# Decoupling_caps.net
KiCad netlist of a schematic drawn in Altium Designer
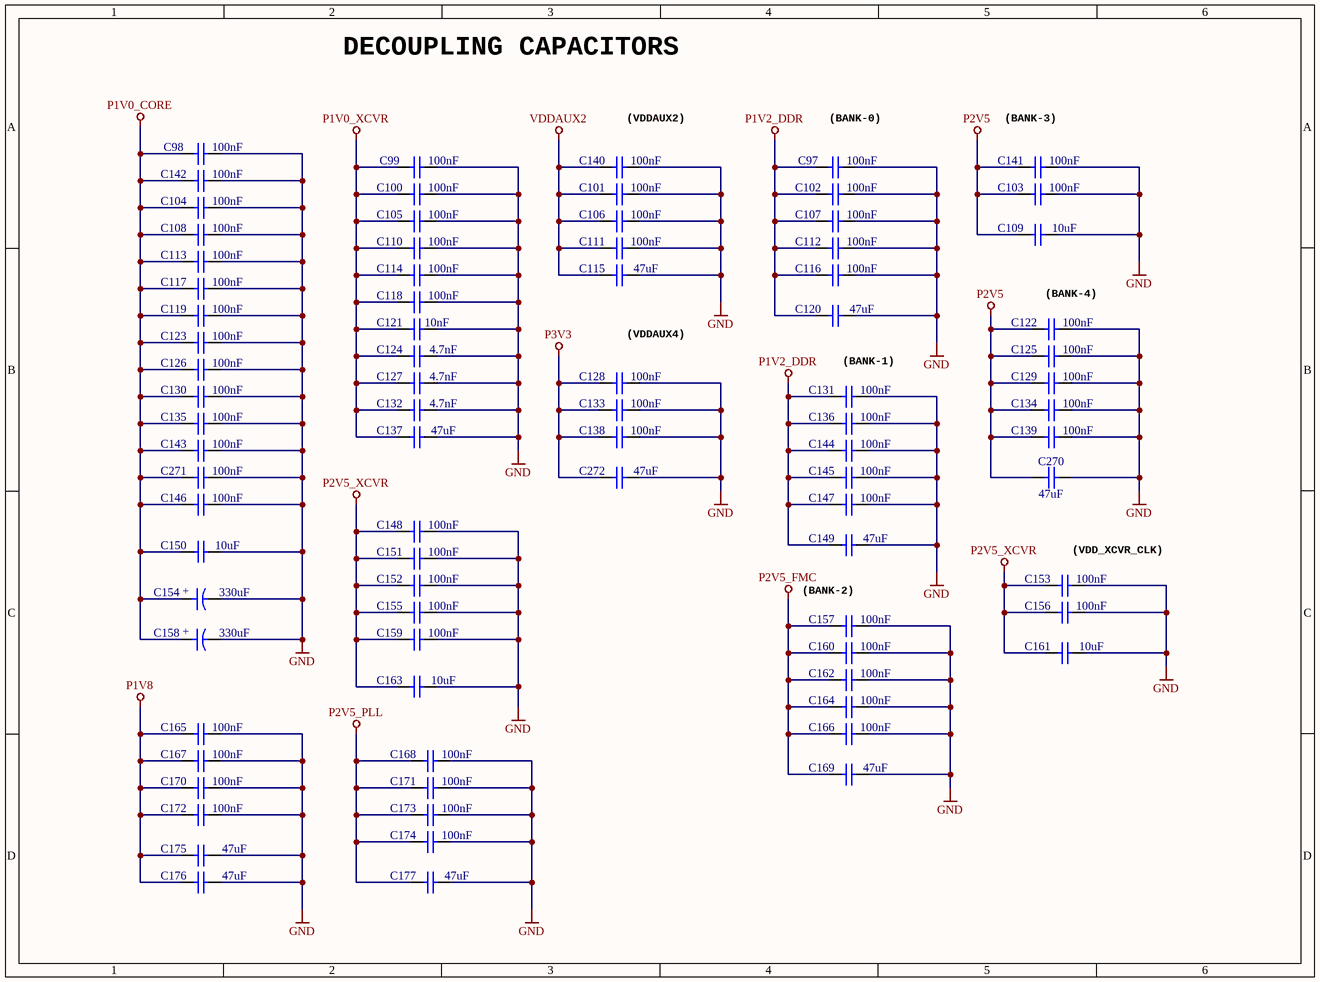
[diagram p0: Decoupling_caps.SchDoc]

(export (version "E")
  (design (tool "Eeschema 10.0.6"))
  (components
    (comp (ref "C97")
      (value "100nF")
      (footprint "CAPC0603X33N")
      (description "Non-polarised capacitor")
      (fields
        (field (name "MANUFACTURER") "GENERIC")
        (field (name "PART NUMBER") "CC0201_100NF_6.3V_10%_X5R")
        (field (name "AUTHOR") "CERN DEM JLC")
      )
      (libsource (lib "Capacitors") (part "Capacitor - non polarized"))
    )
    (comp (ref "C98")
      (value "100nF")
      (footprint "CAPC0603X33N")
      (description "Non-polarised capacitor")
      (fields
        (field (name "MANUFACTURER") "GENERIC")
        (field (name "PART NUMBER") "CC0201_100NF_6.3V_10%_X5R")
        (field (name "AUTHOR") "CERN DEM JLC")
      )
      (libsource (lib "Capacitors") (part "Capacitor - non polarized"))
    )
    (comp (ref "C99")
      (value "100nF")
      (footprint "CAPC0603X33N")
      (description "Non-polarised capacitor")
      (fields
        (field (name "MANUFACTURER") "GENERIC")
        (field (name "PART NUMBER") "CC0201_100NF_6.3V_10%_X5R")
        (field (name "AUTHOR") "CERN DEM JLC")
      )
      (libsource (lib "Capacitors") (part "Capacitor - non polarized"))
    )
    (comp (ref "C100")
      (value "100nF")
      (footprint "CAPC0603X33N")
      (description "Non-polarised capacitor")
      (fields
        (field (name "MANUFACTURER") "GENERIC")
        (field (name "PART NUMBER") "CC0201_100NF_6.3V_10%_X5R")
        (field (name "AUTHOR") "CERN DEM JLC")
      )
      (libsource (lib "Capacitors") (part "Capacitor - non polarized"))
    )
    (comp (ref "C101")
      (value "100nF")
      (footprint "CAPC0603X33N")
      (description "Non-polarised capacitor")
      (fields
        (field (name "MANUFACTURER") "GENERIC")
        (field (name "PART NUMBER") "CC0201_100NF_6.3V_10%_X5R")
        (field (name "AUTHOR") "CERN DEM JLC")
      )
      (libsource (lib "Capacitors") (part "Capacitor - non polarized"))
    )
    (comp (ref "C102")
      (value "100nF")
      (footprint "CAPC0603X33N")
      (description "Non-polarised capacitor")
      (fields
        (field (name "MANUFACTURER") "GENERIC")
        (field (name "PART NUMBER") "CC0201_100NF_6.3V_10%_X5R")
        (field (name "AUTHOR") "CERN DEM JLC")
      )
      (libsource (lib "Capacitors") (part "Capacitor - non polarized"))
    )
    (comp (ref "C103")
      (value "100nF")
      (footprint "CAPC0603X33N")
      (description "Non-polarised capacitor")
      (fields
        (field (name "MANUFACTURER") "GENERIC")
        (field (name "PART NUMBER") "CC0201_100NF_6.3V_10%_X5R")
        (field (name "AUTHOR") "CERN DEM JLC")
      )
      (libsource (lib "Capacitors") (part "Capacitor - non polarized"))
    )
    (comp (ref "C104")
      (value "100nF")
      (footprint "CAPC0603X33N")
      (description "Non-polarised capacitor")
      (fields
        (field (name "MANUFACTURER") "GENERIC")
        (field (name "PART NUMBER") "CC0201_100NF_6.3V_10%_X5R")
        (field (name "AUTHOR") "CERN DEM JLC")
      )
      (libsource (lib "Capacitors") (part "Capacitor - non polarized"))
    )
    (comp (ref "C105")
      (value "100nF")
      (footprint "CAPC0603X33N")
      (description "Non-polarised capacitor")
      (fields
        (field (name "MANUFACTURER") "GENERIC")
        (field (name "PART NUMBER") "CC0201_100NF_6.3V_10%_X5R")
        (field (name "AUTHOR") "CERN DEM JLC")
      )
      (libsource (lib "Capacitors") (part "Capacitor - non polarized"))
    )
    (comp (ref "C106")
      (value "100nF")
      (footprint "CAPC0603X33N")
      (description "Non-polarised capacitor")
      (fields
        (field (name "MANUFACTURER") "GENERIC")
        (field (name "PART NUMBER") "CC0201_100NF_6.3V_10%_X5R")
        (field (name "AUTHOR") "CERN DEM JLC")
      )
      (libsource (lib "Capacitors") (part "Capacitor - non polarized"))
    )
    (comp (ref "C107")
      (value "100nF")
      (footprint "CAPC0603X33N")
      (description "Non-polarised capacitor")
      (fields
        (field (name "MANUFACTURER") "GENERIC")
        (field (name "PART NUMBER") "CC0201_100NF_6.3V_10%_X5R")
        (field (name "AUTHOR") "CERN DEM JLC")
      )
      (libsource (lib "Capacitors") (part "Capacitor - non polarized"))
    )
    (comp (ref "C108")
      (value "100nF")
      (footprint "CAPC0603X33N")
      (description "Non-polarised capacitor")
      (fields
        (field (name "MANUFACTURER") "GENERIC")
        (field (name "PART NUMBER") "CC0201_100NF_6.3V_10%_X5R")
        (field (name "AUTHOR") "CERN DEM JLC")
      )
      (libsource (lib "Capacitors") (part "Capacitor - non polarized"))
    )
    (comp (ref "C109")
      (value "10uF")
      (footprint "CAPC1608X80N")
      (description "Non-polarised capacitor")
      (fields
        (field (name "MANUFACTURER") "GENERIC")
        (field (name "PART NUMBER") "CC0603_10UF_10V_10%_X5R")
        (field (name "AUTHOR") "CERN DEM JLC")
      )
      (libsource (lib "Capacitors") (part "Capacitor - non polarized"))
    )
    (comp (ref "C110")
      (value "100nF")
      (footprint "CAPC0603X33N")
      (description "Non-polarised capacitor")
      (fields
        (field (name "MANUFACTURER") "GENERIC")
        (field (name "PART NUMBER") "CC0201_100NF_6.3V_10%_X5R")
        (field (name "AUTHOR") "CERN DEM JLC")
      )
      (libsource (lib "Capacitors") (part "Capacitor - non polarized"))
    )
    (comp (ref "C111")
      (value "100nF")
      (footprint "CAPC0603X33N")
      (description "Non-polarised capacitor")
      (fields
        (field (name "MANUFACTURER") "GENERIC")
        (field (name "PART NUMBER") "CC0201_100NF_6.3V_10%_X5R")
        (field (name "AUTHOR") "CERN DEM JLC")
      )
      (libsource (lib "Capacitors") (part "Capacitor - non polarized"))
    )
    (comp (ref "C112")
      (value "100nF")
      (footprint "CAPC0603X33N")
      (description "Non-polarised capacitor")
      (fields
        (field (name "MANUFACTURER") "GENERIC")
        (field (name "PART NUMBER") "CC0201_100NF_6.3V_10%_X5R")
        (field (name "AUTHOR") "CERN DEM JLC")
      )
      (libsource (lib "Capacitors") (part "Capacitor - non polarized"))
    )
    (comp (ref "C113")
      (value "100nF")
      (footprint "CAPC0603X33N")
      (description "Non-polarised capacitor")
      (fields
        (field (name "MANUFACTURER") "GENERIC")
        (field (name "PART NUMBER") "CC0201_100NF_6.3V_10%_X5R")
        (field (name "AUTHOR") "CERN DEM JLC")
      )
      (libsource (lib "Capacitors") (part "Capacitor - non polarized"))
    )
    (comp (ref "C114")
      (value "100nF")
      (footprint "CAPC0603X33N")
      (description "Non-polarised capacitor")
      (fields
        (field (name "MANUFACTURER") "GENERIC")
        (field (name "PART NUMBER") "CC0201_100NF_6.3V_10%_X5R")
        (field (name "AUTHOR") "CERN DEM JLC")
      )
      (libsource (lib "Capacitors") (part "Capacitor - non polarized"))
    )
    (comp (ref "C115")
      (value "47uF")
      (footprint "CAPC2012X140N")
      (description "Non-polarised capacitor")
      (fields
        (field (name "PART NUMBER") "CC0805_47UF_6.3V_20%_X5R")
        (field (name "MANUFACTURER") "GENERIC")
        (field (name "AUTHOR") "CERN DEM JLC")
      )
      (libsource (lib "Capacitors") (part "Capacitor - non polarized"))
    )
    (comp (ref "C116")
      (value "100nF")
      (footprint "CAPC0603X33N")
      (description "Non-polarised capacitor")
      (fields
        (field (name "MANUFACTURER") "GENERIC")
        (field (name "PART NUMBER") "CC0201_100NF_6.3V_10%_X5R")
        (field (name "AUTHOR") "CERN DEM JLC")
      )
      (libsource (lib "Capacitors") (part "Capacitor - non polarized"))
    )
    (comp (ref "C117")
      (value "100nF")
      (footprint "CAPC0603X33N")
      (description "Non-polarised capacitor")
      (fields
        (field (name "MANUFACTURER") "GENERIC")
        (field (name "PART NUMBER") "CC0201_100NF_6.3V_10%_X5R")
        (field (name "AUTHOR") "CERN DEM JLC")
      )
      (libsource (lib "Capacitors") (part "Capacitor - non polarized"))
    )
    (comp (ref "C118")
      (value "100nF")
      (footprint "CAPC0603X33N")
      (description "Non-polarised capacitor")
      (fields
        (field (name "MANUFACTURER") "GENERIC")
        (field (name "PART NUMBER") "CC0201_100NF_6.3V_10%_X5R")
        (field (name "AUTHOR") "CERN DEM JLC")
      )
      (libsource (lib "Capacitors") (part "Capacitor - non polarized"))
    )
    (comp (ref "C119")
      (value "100nF")
      (footprint "CAPC0603X33N")
      (description "Non-polarised capacitor")
      (fields
        (field (name "MANUFACTURER") "GENERIC")
        (field (name "PART NUMBER") "CC0201_100NF_6.3V_10%_X5R")
        (field (name "AUTHOR") "CERN DEM JLC")
      )
      (libsource (lib "Capacitors") (part "Capacitor - non polarized"))
    )
    (comp (ref "C120")
      (value "47uF")
      (footprint "CAPC2012X140N")
      (description "Non-polarised capacitor")
      (fields
        (field (name "MANUFACTURER") "GENERIC")
        (field (name "PART NUMBER") "CC0805_47UF_6.3V_20%_X5R")
        (field (name "AUTHOR") "CERN DEM JLC")
      )
      (libsource (lib "Capacitors") (part "Capacitor - non polarized"))
    )
    (comp (ref "C121")
      (value "10nF")
      (footprint "CAPC0603X33N")
      (description "Non-polarised capacitor")
      (fields
        (field (name "MANUFACTURER") "GENERIC")
        (field (name "PART NUMBER") "CC0201_10NF_10V_10%_X5R")
        (field (name "AUTHOR") "CERN DEM JLC")
      )
      (libsource (lib "Capacitors") (part "Capacitor - non polarized"))
    )
    (comp (ref "C122")
      (value "100nF")
      (footprint "CAPC0603X33N")
      (description "Non-polarised capacitor")
      (fields
        (field (name "MANUFACTURER") "GENERIC")
        (field (name "PART NUMBER") "CC0201_100NF_6.3V_10%_X5R")
        (field (name "AUTHOR") "CERN DEM JLC")
      )
      (libsource (lib "Capacitors") (part "Capacitor - non polarized"))
    )
    (comp (ref "C123")
      (value "100nF")
      (footprint "CAPC0603X33N")
      (description "Non-polarised capacitor")
      (fields
        (field (name "MANUFACTURER") "GENERIC")
        (field (name "PART NUMBER") "CC0201_100NF_6.3V_10%_X5R")
        (field (name "AUTHOR") "CERN DEM JLC")
      )
      (libsource (lib "Capacitors") (part "Capacitor - non polarized"))
    )
    (comp (ref "C124")
      (value "4.7nF")
      (footprint "CAPC0603X33N")
      (description "Non-polarised capacitor")
      (fields
        (field (name "MANUFACTURER") "GENERIC")
        (field (name "PART NUMBER") "CC0201_4.7NF_10V_10%_X5R")
        (field (name "AUTHOR") "CERN DEM JLC")
      )
      (libsource (lib "Capacitors") (part "Capacitor - non polarized"))
    )
    (comp (ref "C125")
      (value "100nF")
      (footprint "CAPC0603X33N")
      (description "Non-polarised capacitor")
      (fields
        (field (name "MANUFACTURER") "GENERIC")
        (field (name "PART NUMBER") "CC0201_100NF_6.3V_10%_X5R")
        (field (name "AUTHOR") "CERN DEM JLC")
      )
      (libsource (lib "Capacitors") (part "Capacitor - non polarized"))
    )
    (comp (ref "C126")
      (value "100nF")
      (footprint "CAPC0603X33N")
      (description "Non-polarised capacitor")
      (fields
        (field (name "MANUFACTURER") "GENERIC")
        (field (name "PART NUMBER") "CC0201_100NF_6.3V_10%_X5R")
        (field (name "AUTHOR") "CERN DEM JLC")
      )
      (libsource (lib "Capacitors") (part "Capacitor - non polarized"))
    )
    (comp (ref "C127")
      (value "4.7nF")
      (footprint "CAPC0603X33N")
      (description "Non-polarised capacitor")
      (fields
        (field (name "MANUFACTURER") "GENERIC")
        (field (name "PART NUMBER") "CC0201_4.7NF_10V_10%_X5R")
        (field (name "AUTHOR") "CERN DEM JLC")
      )
      (libsource (lib "Capacitors") (part "Capacitor - non polarized"))
    )
    (comp (ref "C128")
      (value "100nF")
      (footprint "CAPC0603X33N")
      (description "Non-polarised capacitor")
      (fields
        (field (name "MANUFACTURER") "GENERIC")
        (field (name "PART NUMBER") "CC0201_100NF_6.3V_10%_X5R")
        (field (name "AUTHOR") "CERN DEM JLC")
      )
      (libsource (lib "Capacitors") (part "Capacitor - non polarized"))
    )
    (comp (ref "C129")
      (value "100nF")
      (footprint "CAPC0603X33N")
      (description "Non-polarised capacitor")
      (fields
        (field (name "MANUFACTURER") "GENERIC")
        (field (name "PART NUMBER") "CC0201_100NF_6.3V_10%_X5R")
        (field (name "AUTHOR") "CERN DEM JLC")
      )
      (libsource (lib "Capacitors") (part "Capacitor - non polarized"))
    )
    (comp (ref "C130")
      (value "100nF")
      (footprint "CAPC0603X33N")
      (description "Non-polarised capacitor")
      (fields
        (field (name "MANUFACTURER") "GENERIC")
        (field (name "PART NUMBER") "CC0201_100NF_6.3V_10%_X5R")
        (field (name "AUTHOR") "CERN DEM JLC")
      )
      (libsource (lib "Capacitors") (part "Capacitor - non polarized"))
    )
    (comp (ref "C131")
      (value "100nF")
      (footprint "CAPC0603X33N")
      (description "Non-polarised capacitor")
      (fields
        (field (name "MANUFACTURER") "GENERIC")
        (field (name "PART NUMBER") "CC0201_100NF_6.3V_10%_X5R")
        (field (name "AUTHOR") "CERN DEM JLC")
      )
      (libsource (lib "Capacitors") (part "Capacitor - non polarized"))
    )
    (comp (ref "C132")
      (value "4.7nF")
      (footprint "CAPC0603X33N")
      (description "Non-polarised capacitor")
      (fields
        (field (name "MANUFACTURER") "GENERIC")
        (field (name "PART NUMBER") "CC0201_4.7NF_10V_10%_X5R")
        (field (name "AUTHOR") "CERN DEM JLC")
      )
      (libsource (lib "Capacitors") (part "Capacitor - non polarized"))
    )
    (comp (ref "C133")
      (value "100nF")
      (footprint "CAPC0603X33N")
      (description "Non-polarised capacitor")
      (fields
        (field (name "MANUFACTURER") "GENERIC")
        (field (name "PART NUMBER") "CC0201_100NF_6.3V_10%_X5R")
        (field (name "AUTHOR") "CERN DEM JLC")
      )
      (libsource (lib "Capacitors") (part "Capacitor - non polarized"))
    )
    (comp (ref "C134")
      (value "100nF")
      (footprint "CAPC0603X33N")
      (description "Non-polarised capacitor")
      (fields
        (field (name "MANUFACTURER") "GENERIC")
        (field (name "PART NUMBER") "CC0201_100NF_6.3V_10%_X5R")
        (field (name "AUTHOR") "CERN DEM JLC")
      )
      (libsource (lib "Capacitors") (part "Capacitor - non polarized"))
    )
    (comp (ref "C135")
      (value "100nF")
      (footprint "CAPC0603X33N")
      (description "Non-polarised capacitor")
      (fields
        (field (name "MANUFACTURER") "GENERIC")
        (field (name "PART NUMBER") "CC0201_100NF_6.3V_10%_X5R")
        (field (name "AUTHOR") "CERN DEM JLC")
      )
      (libsource (lib "Capacitors") (part "Capacitor - non polarized"))
    )
    (comp (ref "C136")
      (value "100nF")
      (footprint "CAPC0603X33N")
      (description "Non-polarised capacitor")
      (fields
        (field (name "MANUFACTURER") "GENERIC")
        (field (name "PART NUMBER") "CC0201_100NF_6.3V_10%_X5R")
        (field (name "AUTHOR") "CERN DEM JLC")
      )
      (libsource (lib "Capacitors") (part "Capacitor - non polarized"))
    )
    (comp (ref "C137")
      (value "47uF")
      (footprint "CAPC2012X140N")
      (description "Non-polarised capacitor")
      (fields
        (field (name "PART NUMBER") "CC0805_47UF_6.3V_20%_X5R")
        (field (name "MANUFACTURER") "GENERIC")
        (field (name "AUTHOR") "CERN DEM JLC")
      )
      (libsource (lib "Capacitors") (part "Capacitor - non polarized"))
    )
    (comp (ref "C138")
      (value "100nF")
      (footprint "CAPC0603X33N")
      (description "Non-polarised capacitor")
      (fields
        (field (name "MANUFACTURER") "GENERIC")
        (field (name "PART NUMBER") "CC0201_100NF_6.3V_10%_X5R")
        (field (name "AUTHOR") "CERN DEM JLC")
      )
      (libsource (lib "Capacitors") (part "Capacitor - non polarized"))
    )
    (comp (ref "C139")
      (value "100nF")
      (footprint "CAPC0603X33N")
      (description "Non-polarised capacitor")
      (fields
        (field (name "MANUFACTURER") "GENERIC")
        (field (name "PART NUMBER") "CC0201_100NF_6.3V_10%_X5R")
        (field (name "AUTHOR") "CERN DEM JLC")
      )
      (libsource (lib "Capacitors") (part "Capacitor - non polarized"))
    )
    (comp (ref "C140")
      (value "100nF")
      (footprint "CAPC0603X33N")
      (description "Non-polarised capacitor")
      (fields
        (field (name "MANUFACTURER") "GENERIC")
        (field (name "PART NUMBER") "CC0201_100NF_6.3V_10%_X5R")
        (field (name "AUTHOR") "CERN DEM JLC")
      )
      (libsource (lib "Capacitors") (part "Capacitor - non polarized"))
    )
    (comp (ref "C141")
      (value "100nF")
      (footprint "CAPC0603X33N")
      (description "Non-polarised capacitor")
      (fields
        (field (name "MANUFACTURER") "GENERIC")
        (field (name "PART NUMBER") "CC0201_100NF_6.3V_10%_X5R")
        (field (name "AUTHOR") "CERN DEM JLC")
      )
      (libsource (lib "Capacitors") (part "Capacitor - non polarized"))
    )
    (comp (ref "C142")
      (value "100nF")
      (footprint "CAPC0603X33N")
      (description "Non-polarised capacitor")
      (fields
        (field (name "MANUFACTURER") "GENERIC")
        (field (name "PART NUMBER") "CC0201_100NF_6.3V_10%_X5R")
        (field (name "AUTHOR") "CERN DEM JLC")
      )
      (libsource (lib "Capacitors") (part "Capacitor - non polarized"))
    )
    (comp (ref "C143")
      (value "100nF")
      (footprint "CAPC0603X33N")
      (description "Non-polarised capacitor")
      (fields
        (field (name "MANUFACTURER") "GENERIC")
        (field (name "PART NUMBER") "CC0201_100NF_6.3V_10%_X5R")
        (field (name "AUTHOR") "CERN DEM JLC")
      )
      (libsource (lib "Capacitors") (part "Capacitor - non polarized"))
    )
    (comp (ref "C144")
      (value "100nF")
      (footprint "CAPC0603X33N")
      (description "Non-polarised capacitor")
      (fields
        (field (name "MANUFACTURER") "GENERIC")
        (field (name "PART NUMBER") "CC0201_100NF_6.3V_10%_X5R")
        (field (name "AUTHOR") "CERN DEM JLC")
      )
      (libsource (lib "Capacitors") (part "Capacitor - non polarized"))
    )
    (comp (ref "C145")
      (value "100nF")
      (footprint "CAPC0603X33N")
      (description "Non-polarised capacitor")
      (fields
        (field (name "MANUFACTURER") "GENERIC")
        (field (name "PART NUMBER") "CC0201_100NF_6.3V_10%_X5R")
        (field (name "AUTHOR") "CERN DEM JLC")
      )
      (libsource (lib "Capacitors") (part "Capacitor - non polarized"))
    )
    (comp (ref "C146")
      (value "100nF")
      (footprint "CAPC0603X33N")
      (description "Non-polarised capacitor")
      (fields
        (field (name "MANUFACTURER") "GENERIC")
        (field (name "PART NUMBER") "CC0201_100NF_6.3V_10%_X5R")
        (field (name "AUTHOR") "CERN DEM JLC")
      )
      (libsource (lib "Capacitors") (part "Capacitor - non polarized"))
    )
    (comp (ref "C147")
      (value "100nF")
      (footprint "CAPC0603X33N")
      (description "Non-polarised capacitor")
      (fields
        (field (name "MANUFACTURER") "GENERIC")
        (field (name "PART NUMBER") "CC0201_100NF_6.3V_10%_X5R")
        (field (name "AUTHOR") "CERN DEM JLC")
      )
      (libsource (lib "Capacitors") (part "Capacitor - non polarized"))
    )
    (comp (ref "C148")
      (value "100nF")
      (footprint "CAPC0603X33N")
      (description "Non-polarised capacitor")
      (fields
        (field (name "MANUFACTURER") "GENERIC")
        (field (name "PART NUMBER") "CC0201_100NF_6.3V_10%_X5R")
        (field (name "AUTHOR") "CERN DEM JLC")
      )
      (libsource (lib "Capacitors") (part "Capacitor - non polarized"))
    )
    (comp (ref "C149")
      (value "47uF")
      (footprint "CAPC2012X140N")
      (description "Non-polarised capacitor")
      (fields
        (field (name "PART NUMBER") "CC0805_47UF_6.3V_20%_X5R")
        (field (name "MANUFACTURER") "GENERIC")
        (field (name "AUTHOR") "CERN DEM JLC")
      )
      (libsource (lib "Capacitors") (part "Capacitor - non polarized"))
    )
    (comp (ref "C150")
      (value "10uF")
      (footprint "CAPC1608X80N")
      (description "Non-polarised capacitor")
      (fields
        (field (name "MANUFACTURER") "GENERIC")
        (field (name "PART NUMBER") "CC0603_10UF_10V_10%_X5R")
        (field (name "AUTHOR") "CERN DEM JLC")
      )
      (libsource (lib "Capacitors") (part "Capacitor - non polarized"))
    )
    (comp (ref "C151")
      (value "100nF")
      (footprint "CAPC0603X33N")
      (description "Non-polarised capacitor")
      (fields
        (field (name "MANUFACTURER") "GENERIC")
        (field (name "PART NUMBER") "CC0201_100NF_6.3V_10%_X5R")
        (field (name "AUTHOR") "CERN DEM JLC")
      )
      (libsource (lib "Capacitors") (part "Capacitor - non polarized"))
    )
    (comp (ref "C152")
      (value "100nF")
      (footprint "CAPC0603X33N")
      (description "Non-polarised capacitor")
      (fields
        (field (name "MANUFACTURER") "GENERIC")
        (field (name "PART NUMBER") "CC0201_100NF_6.3V_10%_X5R")
        (field (name "AUTHOR") "CERN DEM JLC")
      )
      (libsource (lib "Capacitors") (part "Capacitor - non polarized"))
    )
    (comp (ref "C153")
      (value "100nF")
      (footprint "CAPC0603X33N")
      (description "Non-polarised capacitor")
      (fields
        (field (name "MANUFACTURER") "GENERIC")
        (field (name "PART NUMBER") "CC0201_100NF_6.3V_10%_X5R")
        (field (name "AUTHOR") "CERN DEM JLC")
      )
      (libsource (lib "Capacitors") (part "Capacitor - non polarized"))
    )
    (comp (ref "C154")
      (value "330uF")
      (footprint "CAPMP7343X310N")
      (description "Polarised capacitor")
      (fields
        (field (name "MANUFACTURER") "KEMET")
        (field (name "PART NUMBER") "CTE7343-31_330UF_6.3V_20%_LESR0025_KEMET_T520")
        (field (name "AUTHOR") "CERN DEM JLC")
      )
      (libsource (lib "Capacitors") (part "Capacitor - polarized"))
    )
    (comp (ref "C155")
      (value "100nF")
      (footprint "CAPC0603X33N")
      (description "Non-polarised capacitor")
      (fields
        (field (name "MANUFACTURER") "GENERIC")
        (field (name "PART NUMBER") "CC0201_100NF_6.3V_10%_X5R")
        (field (name "AUTHOR") "CERN DEM JLC")
      )
      (libsource (lib "Capacitors") (part "Capacitor - non polarized"))
    )
    (comp (ref "C156")
      (value "100nF")
      (footprint "CAPC0603X33N")
      (description "Non-polarised capacitor")
      (fields
        (field (name "MANUFACTURER") "GENERIC")
        (field (name "PART NUMBER") "CC0201_100NF_6.3V_10%_X5R")
        (field (name "AUTHOR") "CERN DEM JLC")
      )
      (libsource (lib "Capacitors") (part "Capacitor - non polarized"))
    )
    (comp (ref "C157")
      (value "100nF")
      (footprint "CAPC0603X33N")
      (description "Non-polarised capacitor")
      (fields
        (field (name "MANUFACTURER") "GENERIC")
        (field (name "PART NUMBER") "CC0201_100NF_6.3V_10%_X5R")
        (field (name "AUTHOR") "CERN DEM JLC")
      )
      (libsource (lib "Capacitors") (part "Capacitor - non polarized"))
    )
    (comp (ref "C158")
      (value "330uF")
      (footprint "CAPMP7343X310N")
      (description "Polarised capacitor")
      (fields
        (field (name "MANUFACTURER") "KEMET")
        (field (name "PART NUMBER") "CTE7343-31_330UF_6.3V_20%_LESR0025_KEMET_T520")
        (field (name "AUTHOR") "CERN DEM JLC")
      )
      (libsource (lib "Capacitors") (part "Capacitor - polarized"))
    )
    (comp (ref "C159")
      (value "100nF")
      (footprint "CAPC0603X33N")
      (description "Non-polarised capacitor")
      (fields
        (field (name "MANUFACTURER") "GENERIC")
        (field (name "PART NUMBER") "CC0201_100NF_6.3V_10%_X5R")
        (field (name "AUTHOR") "CERN DEM JLC")
      )
      (libsource (lib "Capacitors") (part "Capacitor - non polarized"))
    )
    (comp (ref "C160")
      (value "100nF")
      (footprint "CAPC0603X33N")
      (description "Non-polarised capacitor")
      (fields
        (field (name "MANUFACTURER") "GENERIC")
        (field (name "PART NUMBER") "CC0201_100NF_6.3V_10%_X5R")
        (field (name "AUTHOR") "CERN DEM JLC")
      )
      (libsource (lib "Capacitors") (part "Capacitor - non polarized"))
    )
    (comp (ref "C161")
      (value "10uF")
      (footprint "CAPC1608X80N")
      (description "Non-polarised capacitor")
      (fields
        (field (name "MANUFACTURER") "GENERIC")
        (field (name "PART NUMBER") "CC0603_10UF_10V_10%_X5R")
        (field (name "AUTHOR") "CERN DEM JLC")
      )
      (libsource (lib "Capacitors") (part "Capacitor - non polarized"))
    )
    (comp (ref "C162")
      (value "100nF")
      (footprint "CAPC0603X33N")
      (description "Non-polarised capacitor")
      (fields
        (field (name "MANUFACTURER") "GENERIC")
        (field (name "PART NUMBER") "CC0201_100NF_6.3V_10%_X5R")
        (field (name "AUTHOR") "CERN DEM JLC")
      )
      (libsource (lib "Capacitors") (part "Capacitor - non polarized"))
    )
    (comp (ref "C163")
      (value "10uF")
      (footprint "CAPC1608X80N")
      (description "Non-polarised capacitor")
      (fields
        (field (name "MANUFACTURER") "GENERIC")
        (field (name "PART NUMBER") "CC0603_10UF_10V_10%_X5R")
        (field (name "AUTHOR") "CERN DEM JLC")
      )
      (libsource (lib "Capacitors") (part "Capacitor - non polarized"))
    )
    (comp (ref "C164")
      (value "100nF")
      (footprint "CAPC0603X33N")
      (description "Non-polarised capacitor")
      (fields
        (field (name "MANUFACTURER") "GENERIC")
        (field (name "PART NUMBER") "CC0201_100NF_6.3V_10%_X5R")
        (field (name "AUTHOR") "CERN DEM JLC")
      )
      (libsource (lib "Capacitors") (part "Capacitor - non polarized"))
    )
    (comp (ref "C165")
      (value "100nF")
      (footprint "CAPC0603X33N")
      (description "Non-polarised capacitor")
      (fields
        (field (name "MANUFACTURER") "GENERIC")
        (field (name "PART NUMBER") "CC0201_100NF_6.3V_10%_X5R")
        (field (name "AUTHOR") "CERN DEM JLC")
      )
      (libsource (lib "Capacitors") (part "Capacitor - non polarized"))
    )
    (comp (ref "C166")
      (value "100nF")
      (footprint "CAPC0603X33N")
      (description "Non-polarised capacitor")
      (fields
        (field (name "MANUFACTURER") "GENERIC")
        (field (name "PART NUMBER") "CC0201_100NF_6.3V_10%_X5R")
        (field (name "AUTHOR") "CERN DEM JLC")
      )
      (libsource (lib "Capacitors") (part "Capacitor - non polarized"))
    )
    (comp (ref "C167")
      (value "100nF")
      (footprint "CAPC0603X33N")
      (description "Non-polarised capacitor")
      (fields
        (field (name "MANUFACTURER") "GENERIC")
        (field (name "PART NUMBER") "CC0201_100NF_6.3V_10%_X5R")
        (field (name "AUTHOR") "CERN DEM JLC")
      )
      (libsource (lib "Capacitors") (part "Capacitor - non polarized"))
    )
    (comp (ref "C168")
      (value "100nF")
      (footprint "CAPC0603X33N")
      (description "Non-polarised capacitor")
      (fields
        (field (name "MANUFACTURER") "GENERIC")
        (field (name "PART NUMBER") "CC0201_100NF_6.3V_10%_X5R")
        (field (name "AUTHOR") "CERN DEM JLC")
      )
      (libsource (lib "Capacitors") (part "Capacitor - non polarized"))
    )
    (comp (ref "C169")
      (value "47uF")
      (footprint "CAPC2012X140N")
      (description "Non-polarised capacitor")
      (fields
        (field (name "MANUFACTURER") "GENERIC")
        (field (name "PART NUMBER") "CC0805_47UF_6.3V_20%_X5R")
        (field (name "AUTHOR") "CERN DEM JLC")
      )
      (libsource (lib "Capacitors") (part "Capacitor - non polarized"))
    )
    (comp (ref "C170")
      (value "100nF")
      (footprint "CAPC0603X33N")
      (description "Non-polarised capacitor")
      (fields
        (field (name "MANUFACTURER") "GENERIC")
        (field (name "PART NUMBER") "CC0201_100NF_6.3V_10%_X5R")
        (field (name "AUTHOR") "CERN DEM JLC")
      )
      (libsource (lib "Capacitors") (part "Capacitor - non polarized"))
    )
    (comp (ref "C171")
      (value "100nF")
      (footprint "CAPC0603X33N")
      (description "Non-polarised capacitor")
      (fields
        (field (name "MANUFACTURER") "GENERIC")
        (field (name "PART NUMBER") "CC0201_100NF_6.3V_10%_X5R")
        (field (name "AUTHOR") "CERN DEM JLC")
      )
      (libsource (lib "Capacitors") (part "Capacitor - non polarized"))
    )
    (comp (ref "C172")
      (value "100nF")
      (footprint "CAPC0603X33N")
      (description "Non-polarised capacitor")
      (fields
        (field (name "MANUFACTURER") "GENERIC")
        (field (name "PART NUMBER") "CC0201_100NF_6.3V_10%_X5R")
        (field (name "AUTHOR") "CERN DEM JLC")
      )
      (libsource (lib "Capacitors") (part "Capacitor - non polarized"))
    )
    (comp (ref "C173")
      (value "100nF")
      (footprint "CAPC0603X33N")
      (description "Non-polarised capacitor")
      (fields
        (field (name "MANUFACTURER") "GENERIC")
        (field (name "PART NUMBER") "CC0201_100NF_6.3V_10%_X5R")
        (field (name "AUTHOR") "CERN DEM JLC")
      )
      (libsource (lib "Capacitors") (part "Capacitor - non polarized"))
    )
    (comp (ref "C174")
      (value "100nF")
      (footprint "CAPC0603X33N")
      (description "Non-polarised capacitor")
      (fields
        (field (name "MANUFACTURER") "GENERIC")
        (field (name "PART NUMBER") "CC0201_100NF_6.3V_10%_X5R")
        (field (name "AUTHOR") "CERN DEM JLC")
      )
      (libsource (lib "Capacitors") (part "Capacitor - non polarized"))
    )
    (comp (ref "C175")
      (value "47uF")
      (footprint "CAPC2012X140N")
      (description "Non-polarised capacitor")
      (fields
        (field (name "PART NUMBER") "CC0805_47UF_6.3V_20%_X5R")
        (field (name "MANUFACTURER") "GENERIC")
        (field (name "AUTHOR") "CERN DEM JLC")
      )
      (libsource (lib "Capacitors") (part "Capacitor - non polarized"))
    )
    (comp (ref "C176")
      (value "47uF")
      (footprint "CAPC2012X140N")
      (description "Non-polarised capacitor")
      (fields
        (field (name "PART NUMBER") "CC0805_47UF_6.3V_20%_X5R")
        (field (name "MANUFACTURER") "GENERIC")
        (field (name "AUTHOR") "CERN DEM JLC")
      )
      (libsource (lib "Capacitors") (part "Capacitor - non polarized"))
    )
    (comp (ref "C177")
      (value "47uF")
      (footprint "CAPC2012X140N")
      (description "Non-polarised capacitor")
      (fields
        (field (name "PART NUMBER") "CC0805_47UF_6.3V_20%_X5R")
        (field (name "MANUFACTURER") "GENERIC")
        (field (name "AUTHOR") "CERN DEM JLC")
      )
      (libsource (lib "Capacitors") (part "Capacitor - non polarized"))
    )
    (comp (ref "C270")
      (value "47uF")
      (footprint "CAPC2012X140N")
      (description "Non-polarised capacitor")
      (fields
        (field (name "PART NUMBER") "CC0805_47UF_6.3V_20%_X5R")
        (field (name "MANUFACTURER") "GENERIC")
        (field (name "AUTHOR") "CERN DEM JLC")
      )
      (libsource (lib "Capacitors") (part "Capacitor - non polarized"))
    )
    (comp (ref "C271")
      (value "100nF")
      (footprint "CAPC0603X33N")
      (description "Non-polarised capacitor")
      (fields
        (field (name "MANUFACTURER") "GENERIC")
        (field (name "PART NUMBER") "CC0201_100NF_6.3V_10%_X5R")
        (field (name "AUTHOR") "CERN DEM JLC")
      )
      (libsource (lib "Capacitors") (part "Capacitor - non polarized"))
    )
    (comp (ref "C272")
      (value "47uF")
      (footprint "CAPC2012X140N")
      (description "Non-polarised capacitor")
      (fields
        (field (name "PART NUMBER") "CC0805_47UF_6.3V_20%_X5R")
        (field (name "MANUFACTURER") "GENERIC")
        (field (name "AUTHOR") "CERN DEM JLC")
      )
      (libsource (lib "Capacitors") (part "Capacitor - non polarized"))
    )
  )
  (nets
    (net (code "1") (name "GND") (class "Default")
      (node (ref "C100") (pin "2") (pinfunction "2_2") (pintype "passive"))
      (node (ref "C101") (pin "2") (pinfunction "2_2") (pintype "passive"))
      (node (ref "C102") (pin "2") (pinfunction "2_2") (pintype "passive"))
      (node (ref "C103") (pin "2") (pinfunction "2_2") (pintype "passive"))
      (node (ref "C104") (pin "2") (pinfunction "2_2") (pintype "passive"))
      (node (ref "C105") (pin "2") (pinfunction "2_2") (pintype "passive"))
      (node (ref "C106") (pin "2") (pinfunction "2_2") (pintype "passive"))
      (node (ref "C107") (pin "2") (pinfunction "2_2") (pintype "passive"))
      (node (ref "C108") (pin "2") (pinfunction "2_2") (pintype "passive"))
      (node (ref "C109") (pin "2") (pinfunction "2_2") (pintype "passive"))
      (node (ref "C110") (pin "2") (pinfunction "2_2") (pintype "passive"))
      (node (ref "C111") (pin "2") (pinfunction "2_2") (pintype "passive"))
      (node (ref "C112") (pin "2") (pinfunction "2_2") (pintype "passive"))
      (node (ref "C113") (pin "2") (pinfunction "2_2") (pintype "passive"))
      (node (ref "C114") (pin "2") (pinfunction "2_2") (pintype "passive"))
      (node (ref "C115") (pin "2") (pinfunction "2_2") (pintype "passive"))
      (node (ref "C116") (pin "2") (pinfunction "2_2") (pintype "passive"))
      (node (ref "C117") (pin "2") (pinfunction "2_2") (pintype "passive"))
      (node (ref "C118") (pin "2") (pinfunction "2_2") (pintype "passive"))
      (node (ref "C119") (pin "2") (pinfunction "2_2") (pintype "passive"))
      (node (ref "C120") (pin "2") (pinfunction "2_2") (pintype "passive"))
      (node (ref "C121") (pin "2") (pinfunction "2_2") (pintype "passive"))
      (node (ref "C122") (pin "2") (pinfunction "2_2") (pintype "passive"))
      (node (ref "C123") (pin "2") (pinfunction "2_2") (pintype "passive"))
      (node (ref "C124") (pin "2") (pinfunction "2_2") (pintype "passive"))
      (node (ref "C125") (pin "2") (pinfunction "2_2") (pintype "passive"))
      (node (ref "C126") (pin "2") (pinfunction "2_2") (pintype "passive"))
      (node (ref "C127") (pin "2") (pinfunction "2_2") (pintype "passive"))
      (node (ref "C128") (pin "2") (pinfunction "2_2") (pintype "passive"))
      (node (ref "C129") (pin "2") (pinfunction "2_2") (pintype "passive"))
      (node (ref "C130") (pin "2") (pinfunction "2_2") (pintype "passive"))
      (node (ref "C131") (pin "2") (pinfunction "2_2") (pintype "passive"))
      (node (ref "C132") (pin "2") (pinfunction "2_2") (pintype "passive"))
      (node (ref "C133") (pin "2") (pinfunction "2_2") (pintype "passive"))
      (node (ref "C134") (pin "2") (pinfunction "2_2") (pintype "passive"))
      (node (ref "C135") (pin "2") (pinfunction "2_2") (pintype "passive"))
      (node (ref "C136") (pin "2") (pinfunction "2_2") (pintype "passive"))
      (node (ref "C137") (pin "2") (pinfunction "2_2") (pintype "passive"))
      (node (ref "C138") (pin "2") (pinfunction "2_2") (pintype "passive"))
      (node (ref "C139") (pin "2") (pinfunction "2_2") (pintype "passive"))
      (node (ref "C140") (pin "2") (pinfunction "2_2") (pintype "passive"))
      (node (ref "C141") (pin "2") (pinfunction "2_2") (pintype "passive"))
      (node (ref "C142") (pin "2") (pinfunction "2_2") (pintype "passive"))
      (node (ref "C143") (pin "2") (pinfunction "2_2") (pintype "passive"))
      (node (ref "C144") (pin "2") (pinfunction "2_2") (pintype "passive"))
      (node (ref "C145") (pin "2") (pinfunction "2_2") (pintype "passive"))
      (node (ref "C146") (pin "2") (pinfunction "2_2") (pintype "passive"))
      (node (ref "C147") (pin "2") (pinfunction "2_2") (pintype "passive"))
      (node (ref "C148") (pin "2") (pinfunction "2_2") (pintype "passive"))
      (node (ref "C149") (pin "2") (pinfunction "2_2") (pintype "passive"))
      (node (ref "C150") (pin "2") (pinfunction "2_2") (pintype "passive"))
      (node (ref "C151") (pin "2") (pinfunction "2_2") (pintype "passive"))
      (node (ref "C152") (pin "2") (pinfunction "2_2") (pintype "passive"))
      (node (ref "C153") (pin "2") (pinfunction "2_2") (pintype "passive"))
      (node (ref "C154") (pin "2") (pinfunction "2_2") (pintype "passive"))
      (node (ref "C155") (pin "2") (pinfunction "2_2") (pintype "passive"))
      (node (ref "C156") (pin "2") (pinfunction "2_2") (pintype "passive"))
      (node (ref "C157") (pin "2") (pinfunction "2_2") (pintype "passive"))
      (node (ref "C158") (pin "2") (pinfunction "2_2") (pintype "passive"))
      (node (ref "C159") (pin "2") (pinfunction "2_2") (pintype "passive"))
      (node (ref "C160") (pin "2") (pinfunction "2_2") (pintype "passive"))
      (node (ref "C161") (pin "2") (pinfunction "2_2") (pintype "passive"))
      (node (ref "C162") (pin "2") (pinfunction "2_2") (pintype "passive"))
      (node (ref "C163") (pin "2") (pinfunction "2_2") (pintype "passive"))
      (node (ref "C164") (pin "2") (pinfunction "2_2") (pintype "passive"))
      (node (ref "C165") (pin "2") (pinfunction "2_2") (pintype "passive"))
      (node (ref "C166") (pin "2") (pinfunction "2_2") (pintype "passive"))
      (node (ref "C167") (pin "2") (pinfunction "2_2") (pintype "passive"))
      (node (ref "C168") (pin "2") (pinfunction "2_2") (pintype "passive"))
      (node (ref "C169") (pin "2") (pinfunction "2_2") (pintype "passive"))
      (node (ref "C170") (pin "2") (pinfunction "2_2") (pintype "passive"))
      (node (ref "C171") (pin "2") (pinfunction "2_2") (pintype "passive"))
      (node (ref "C172") (pin "2") (pinfunction "2_2") (pintype "passive"))
      (node (ref "C173") (pin "2") (pinfunction "2_2") (pintype "passive"))
      (node (ref "C174") (pin "2") (pinfunction "2_2") (pintype "passive"))
      (node (ref "C175") (pin "2") (pinfunction "2_2") (pintype "passive"))
      (node (ref "C176") (pin "2") (pinfunction "2_2") (pintype "passive"))
      (node (ref "C177") (pin "2") (pinfunction "2_2") (pintype "passive"))
      (node (ref "C270") (pin "2") (pinfunction "2_2") (pintype "passive"))
      (node (ref "C271") (pin "2") (pinfunction "2_2") (pintype "passive"))
      (node (ref "C272") (pin "2") (pinfunction "2_2") (pintype "passive"))
      (node (ref "C97") (pin "2") (pinfunction "2_2") (pintype "passive"))
      (node (ref "C98") (pin "2") (pinfunction "2_2") (pintype "passive"))
      (node (ref "C99") (pin "2") (pinfunction "2_2") (pintype "passive"))
    )
    (net (code "2") (name "P1V0_CORE") (class "Default")
      (node (ref "C104") (pin "1") (pinfunction "1_1") (pintype "passive"))
      (node (ref "C108") (pin "1") (pinfunction "1_1") (pintype "passive"))
      (node (ref "C113") (pin "1") (pinfunction "1_1") (pintype "passive"))
      (node (ref "C117") (pin "1") (pinfunction "1_1") (pintype "passive"))
      (node (ref "C119") (pin "1") (pinfunction "1_1") (pintype "passive"))
      (node (ref "C123") (pin "1") (pinfunction "1_1") (pintype "passive"))
      (node (ref "C126") (pin "1") (pinfunction "1_1") (pintype "passive"))
      (node (ref "C130") (pin "1") (pinfunction "1_1") (pintype "passive"))
      (node (ref "C135") (pin "1") (pinfunction "1_1") (pintype "passive"))
      (node (ref "C142") (pin "1") (pinfunction "1_1") (pintype "passive"))
      (node (ref "C143") (pin "1") (pinfunction "1_1") (pintype "passive"))
      (node (ref "C146") (pin "1") (pinfunction "1_1") (pintype "passive"))
      (node (ref "C150") (pin "1") (pinfunction "1_1") (pintype "passive"))
      (node (ref "C154") (pin "1") (pinfunction "1_1") (pintype "passive"))
      (node (ref "C158") (pin "1") (pinfunction "1_1") (pintype "passive"))
      (node (ref "C271") (pin "1") (pinfunction "1_1") (pintype "passive"))
      (node (ref "C98") (pin "1") (pinfunction "1_1") (pintype "passive"))
    )
    (net (code "3") (name "P1V0_XCVR") (class "Default")
      (node (ref "C100") (pin "1") (pinfunction "1_1") (pintype "passive"))
      (node (ref "C105") (pin "1") (pinfunction "1_1") (pintype "passive"))
      (node (ref "C110") (pin "1") (pinfunction "1_1") (pintype "passive"))
      (node (ref "C114") (pin "1") (pinfunction "1_1") (pintype "passive"))
      (node (ref "C118") (pin "1") (pinfunction "1_1") (pintype "passive"))
      (node (ref "C121") (pin "1") (pinfunction "1_1") (pintype "passive"))
      (node (ref "C124") (pin "1") (pinfunction "1_1") (pintype "passive"))
      (node (ref "C127") (pin "1") (pinfunction "1_1") (pintype "passive"))
      (node (ref "C132") (pin "1") (pinfunction "1_1") (pintype "passive"))
      (node (ref "C137") (pin "1") (pinfunction "1_1") (pintype "passive"))
      (node (ref "C99") (pin "1") (pinfunction "1_1") (pintype "passive"))
    )
    (net (code "4") (name "P1V2_DDR") (class "Default")
      (node (ref "C102") (pin "1") (pinfunction "1_1") (pintype "passive"))
      (node (ref "C107") (pin "1") (pinfunction "1_1") (pintype "passive"))
      (node (ref "C112") (pin "1") (pinfunction "1_1") (pintype "passive"))
      (node (ref "C116") (pin "1") (pinfunction "1_1") (pintype "passive"))
      (node (ref "C120") (pin "1") (pinfunction "1_1") (pintype "passive"))
      (node (ref "C131") (pin "1") (pinfunction "1_1") (pintype "passive"))
      (node (ref "C136") (pin "1") (pinfunction "1_1") (pintype "passive"))
      (node (ref "C144") (pin "1") (pinfunction "1_1") (pintype "passive"))
      (node (ref "C145") (pin "1") (pinfunction "1_1") (pintype "passive"))
      (node (ref "C147") (pin "1") (pinfunction "1_1") (pintype "passive"))
      (node (ref "C149") (pin "1") (pinfunction "1_1") (pintype "passive"))
      (node (ref "C97") (pin "1") (pinfunction "1_1") (pintype "passive"))
    )
    (net (code "5") (name "P1V8") (class "Default")
      (node (ref "C165") (pin "1") (pinfunction "1_1") (pintype "passive"))
      (node (ref "C167") (pin "1") (pinfunction "1_1") (pintype "passive"))
      (node (ref "C170") (pin "1") (pinfunction "1_1") (pintype "passive"))
      (node (ref "C172") (pin "1") (pinfunction "1_1") (pintype "passive"))
      (node (ref "C175") (pin "1") (pinfunction "1_1") (pintype "passive"))
      (node (ref "C176") (pin "1") (pinfunction "1_1") (pintype "passive"))
    )
    (net (code "6") (name "P2V5") (class "Default")
      (node (ref "C103") (pin "1") (pinfunction "1_1") (pintype "passive"))
      (node (ref "C109") (pin "1") (pinfunction "1_1") (pintype "passive"))
      (node (ref "C122") (pin "1") (pinfunction "1_1") (pintype "passive"))
      (node (ref "C125") (pin "1") (pinfunction "1_1") (pintype "passive"))
      (node (ref "C129") (pin "1") (pinfunction "1_1") (pintype "passive"))
      (node (ref "C134") (pin "1") (pinfunction "1_1") (pintype "passive"))
      (node (ref "C139") (pin "1") (pinfunction "1_1") (pintype "passive"))
      (node (ref "C141") (pin "1") (pinfunction "1_1") (pintype "passive"))
      (node (ref "C270") (pin "1") (pinfunction "1_1") (pintype "passive"))
    )
    (net (code "7") (name "P2V5_FMC") (class "Default")
      (node (ref "C157") (pin "1") (pinfunction "1_1") (pintype "passive"))
      (node (ref "C160") (pin "1") (pinfunction "1_1") (pintype "passive"))
      (node (ref "C162") (pin "1") (pinfunction "1_1") (pintype "passive"))
      (node (ref "C164") (pin "1") (pinfunction "1_1") (pintype "passive"))
      (node (ref "C166") (pin "1") (pinfunction "1_1") (pintype "passive"))
      (node (ref "C169") (pin "1") (pinfunction "1_1") (pintype "passive"))
    )
    (net (code "8") (name "P2V5_PLL") (class "Default")
      (node (ref "C168") (pin "1") (pinfunction "1_1") (pintype "passive"))
      (node (ref "C171") (pin "1") (pinfunction "1_1") (pintype "passive"))
      (node (ref "C173") (pin "1") (pinfunction "1_1") (pintype "passive"))
      (node (ref "C174") (pin "1") (pinfunction "1_1") (pintype "passive"))
      (node (ref "C177") (pin "1") (pinfunction "1_1") (pintype "passive"))
    )
    (net (code "9") (name "P2V5_XCVR") (class "Default")
      (node (ref "C148") (pin "1") (pinfunction "1_1") (pintype "passive"))
      (node (ref "C151") (pin "1") (pinfunction "1_1") (pintype "passive"))
      (node (ref "C152") (pin "1") (pinfunction "1_1") (pintype "passive"))
      (node (ref "C153") (pin "1") (pinfunction "1_1") (pintype "passive"))
      (node (ref "C155") (pin "1") (pinfunction "1_1") (pintype "passive"))
      (node (ref "C156") (pin "1") (pinfunction "1_1") (pintype "passive"))
      (node (ref "C159") (pin "1") (pinfunction "1_1") (pintype "passive"))
      (node (ref "C161") (pin "1") (pinfunction "1_1") (pintype "passive"))
      (node (ref "C163") (pin "1") (pinfunction "1_1") (pintype "passive"))
    )
    (net (code "10") (name "P3V3") (class "Default")
      (node (ref "C128") (pin "1") (pinfunction "1_1") (pintype "passive"))
      (node (ref "C133") (pin "1") (pinfunction "1_1") (pintype "passive"))
      (node (ref "C138") (pin "1") (pinfunction "1_1") (pintype "passive"))
      (node (ref "C272") (pin "1") (pinfunction "1_1") (pintype "passive"))
    )
    (net (code "11") (name "VDDAUX2") (class "Default")
      (node (ref "C101") (pin "1") (pinfunction "1_1") (pintype "passive"))
      (node (ref "C106") (pin "1") (pinfunction "1_1") (pintype "passive"))
      (node (ref "C111") (pin "1") (pinfunction "1_1") (pintype "passive"))
      (node (ref "C115") (pin "1") (pinfunction "1_1") (pintype "passive"))
      (node (ref "C140") (pin "1") (pinfunction "1_1") (pintype "passive"))
    )
  )
)
